# Vcc5V.net
KiCad netlist of a schematic drawn in Altium Designer
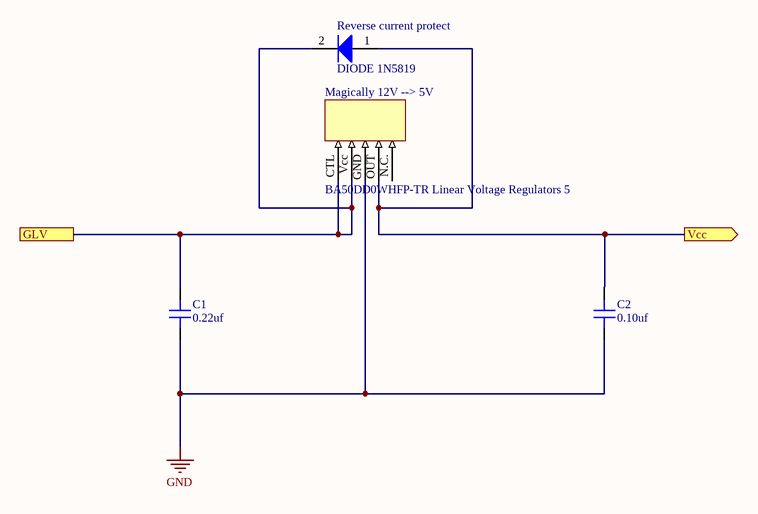
[diagram p0: Vcc5V.SchDoc]

(export (version "E")
  (design (tool "Eeschema 10.0.6"))
  (components
    (comp (ref "C1")
      (value "0.22uf")
      (footprint "CAP 0402/1005")
      (fields
        (field (name "Comment") "Capacitor MLCC 0.22uf 16V CAP 0402/1005")
        (field (name "CREATED_BY") "Nick Mah")
      )
      (libsource (lib "Altium-Lib") (part "Capacitor"))
    )
    (comp (ref "C2")
      (value "0.10uf")
      (footprint "CAP 0402/1005")
      (fields
        (field (name "Comment") "Capacitor MLCC 0.10uf 16V CAP 0402/1005")
        (field (name "CREATED_BY") "Nick Mah")
      )
      (libsource (lib "Altium-Lib") (part "Capacitor"))
    )
    (comp (ref "Magically 12V --> 5V")
      (value "BA50DD0WHFP-TR Linear Voltage Regulators 5")
      (footprint "HRP5")
      (libsource (lib "Altium-Lib") (part "BA50DD0WHFP-TR Linear Voltage Regulators 5"))
    )
    (comp (ref "Reverse current protect")
      (value "DIODE 1N5819")
      (footprint "DIODE DO-214AC(SMA)")
      (fields (field (name "POWER") "40V"))
      (libsource (lib "Altium-Lib") (part "DIODE 1N5819"))
    )
  )
  (nets
    (net (code "1") (name "/GLV") (class "Default")
      (node (ref "C1") (pin "2") (pinfunction "2_2") (pintype "passive"))
      (node (ref "Magically 12V --> 5V") (pin "CTL") (pintype "input"))
      (node (ref "Magically 12V --> 5V") (pin "Vcc") (pintype "input"))
      (node (ref "Reverse current protect") (pin "2") (pinfunction "K_2") (pintype "passive"))
    )
    (net (code "2") (name "/Vcc") (class "Default")
      (node (ref "C2") (pin "2") (pinfunction "2_2") (pintype "passive"))
      (node (ref "Magically 12V --> 5V") (pin "OUT") (pintype "input"))
      (node (ref "Reverse current protect") (pin "1") (pinfunction "A_1") (pintype "passive"))
    )
    (net (code "3") (name "GND") (class "Default")
      (node (ref "C1") (pin "1") (pinfunction "1_1") (pintype "passive"))
      (node (ref "C2") (pin "1") (pinfunction "1_1") (pintype "passive"))
      (node (ref "Magically 12V --> 5V") (pin "GND") (pintype "input"))
    )
    (net (code "4") (name "unconnected-(Magically 12V --> 5V-PadN.C.)") (class "Default")
      (node (ref "Magically 12V --> 5V") (pin "N.C.") (pintype "input"))
    )
  )
)
